# modbransv0_4_2.net
KiCad netlist of a schematic drawn in EAGLE
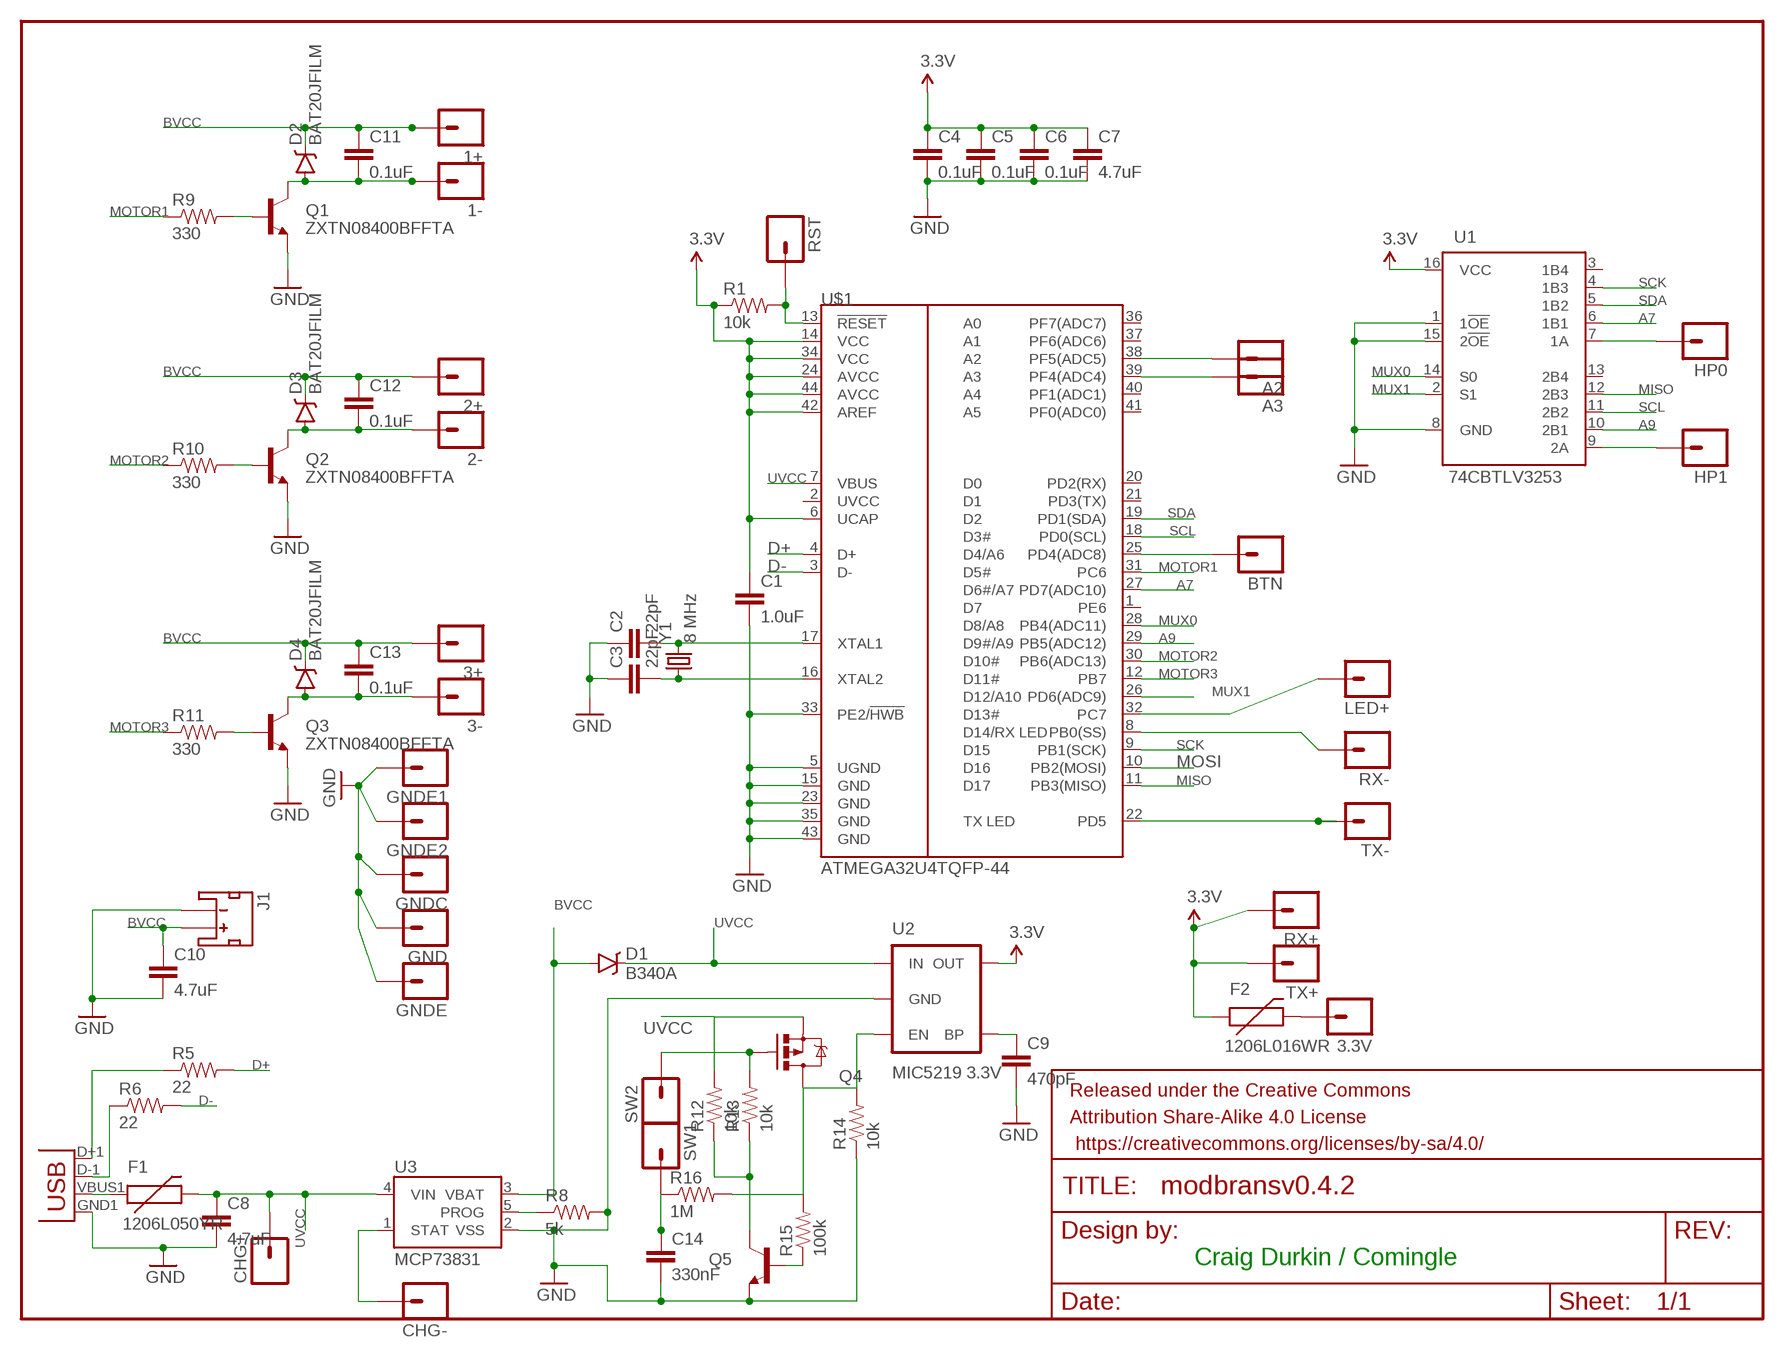
[diagram p0: schematic, sheet 1]

(export (version "E")
  (design (tool "Eeschema 10.0.6"))
  (components
    (comp (ref "1+")
      (value "M01PTH")
      (footprint "eagle-import:1X01")
      (libsource (lib "eagle-import") (part "M01PTH"))
    )
    (comp (ref "1-")
      (value "M01PTH")
      (footprint "eagle-import:1X01")
      (libsource (lib "eagle-import") (part "M01PTH"))
    )
    (comp (ref "2+")
      (value "M01PTH")
      (footprint "eagle-import:1X01")
      (libsource (lib "eagle-import") (part "M01PTH"))
    )
    (comp (ref "2-")
      (value "M01PTH")
      (footprint "eagle-import:1X01")
      (libsource (lib "eagle-import") (part "M01PTH"))
    )
    (comp (ref "3+")
      (value "M01PTH")
      (footprint "eagle-import:1X01")
      (libsource (lib "eagle-import") (part "M01PTH"))
    )
    (comp (ref "3-")
      (value "M01PTH")
      (footprint "eagle-import:1X01")
      (libsource (lib "eagle-import") (part "M01PTH"))
    )
    (comp (ref "3.3V")
      (value "M01PTH")
      (footprint "eagle-import:1X01")
      (libsource (lib "eagle-import") (part "M01PTH"))
    )
    (comp (ref "A2")
      (value "M01PTH")
      (footprint "eagle-import:1X01")
      (libsource (lib "eagle-import") (part "M01PTH"))
    )
    (comp (ref "A3")
      (value "M01PTH")
      (footprint "eagle-import:1X01")
      (libsource (lib "eagle-import") (part "M01PTH"))
    )
    (comp (ref "BTN")
      (value "M01PTH")
      (footprint "eagle-import:1X01")
      (libsource (lib "eagle-import") (part "M01PTH"))
    )
    (comp (ref "C1")
      (value "1.0uF")
      (footprint "eagle-import:0603-CAP")
      (libsource (lib "eagle-import") (part "CAP0603-CAP"))
    )
    (comp (ref "C2")
      (value "22pF")
      (footprint "eagle-import:0603-CAP")
      (libsource (lib "eagle-import") (part "CAP0603-CAP"))
    )
    (comp (ref "C3")
      (value "22pF")
      (footprint "eagle-import:0603-CAP")
      (libsource (lib "eagle-import") (part "CAP0603-CAP"))
    )
    (comp (ref "C4")
      (value "0.1uF")
      (footprint "eagle-import:0603-CAP")
      (libsource (lib "eagle-import") (part "SparkFun-Passives_CAP0603-CAP"))
    )
    (comp (ref "C5")
      (value "0.1uF")
      (footprint "eagle-import:0603-CAP")
      (libsource (lib "eagle-import") (part "SparkFun-Passives_CAP0603-CAP"))
    )
    (comp (ref "C6")
      (value "0.1uF")
      (footprint "eagle-import:0603-CAP")
      (libsource (lib "eagle-import") (part "SparkFun-Passives_CAP0603-CAP"))
    )
    (comp (ref "C7")
      (value "4.7uF")
      (footprint "eagle-import:0603-CAP")
      (libsource (lib "eagle-import") (part "SparkFun-Passives_CAP0603-CAP"))
    )
    (comp (ref "C8")
      (value "4.7uF")
      (footprint "eagle-import:1206")
      (libsource (lib "eagle-import") (part "SparkFun-Passives_CAP1206"))
    )
    (comp (ref "C9")
      (value "470pF")
      (footprint "eagle-import:0603-CAP")
      (libsource (lib "eagle-import") (part "CAP0603-CAP"))
    )
    (comp (ref "C10")
      (value "4.7uF")
      (footprint "eagle-import:1206")
      (libsource (lib "eagle-import") (part "SparkFun-Passives_CAP1206"))
    )
    (comp (ref "C11")
      (value "0.1uF")
      (footprint "eagle-import:0603-CAP")
      (libsource (lib "eagle-import") (part "CAP0603-CAP"))
    )
    (comp (ref "C12")
      (value "0.1uF")
      (footprint "eagle-import:0603-CAP")
      (libsource (lib "eagle-import") (part "CAP0603-CAP"))
    )
    (comp (ref "C13")
      (value "0.1uF")
      (footprint "eagle-import:0603-CAP")
      (libsource (lib "eagle-import") (part "CAP0603-CAP"))
    )
    (comp (ref "C14")
      (value "330nF")
      (footprint "eagle-import:0603-CAP")
      (libsource (lib "eagle-import") (part "CAP0603-CAP"))
    )
    (comp (ref "CHG+")
      (value "M01PTH")
      (footprint "eagle-import:1X01")
      (libsource (lib "eagle-import") (part "M01PTH"))
    )
    (comp (ref "CHG-")
      (value "M01PTH")
      (footprint "eagle-import:1X01")
      (libsource (lib "eagle-import") (part "M01PTH"))
    )
    (comp (ref "D1")
      (value "B340A")
      (footprint "eagle-import:SMA-DIODE")
      (libsource (lib "eagle-import") (part "DIODE-SCHOTTKY-B340A"))
    )
    (comp (ref "D2")
      (value "BAT20JFILM")
      (footprint "eagle-import:SOD-323")
      (libsource (lib "eagle-import") (part "BAT20JFILM"))
    )
    (comp (ref "D3")
      (value "BAT20JFILM")
      (footprint "eagle-import:SOD-323")
      (libsource (lib "eagle-import") (part "BAT20JFILM"))
    )
    (comp (ref "D4")
      (value "BAT20JFILM")
      (footprint "eagle-import:SOD-323")
      (libsource (lib "eagle-import") (part "BAT20JFILM"))
    )
    (comp (ref "F1")
      (value "1206L050YR")
      (footprint "eagle-import:PTC-1206")
      (libsource (lib "eagle-import") (part "PTCSMD"))
    )
    (comp (ref "F2")
      (value "1206L016WR")
      (footprint "eagle-import:PTC-1206")
      (libsource (lib "eagle-import") (part "PTCSMD"))
    )
    (comp (ref "FRAME1")
      (value "FRAME-LETTER")
      (footprint "eagle-import:CREATIVE_COMMONS")
      (libsource (lib "eagle-import") (part "FRAME-LETTER"))
    )
    (comp (ref "GND")
      (value "M01PTH")
      (footprint "eagle-import:1X01")
      (libsource (lib "eagle-import") (part "M01PTH"))
    )
    (comp (ref "GNDC")
      (value "M01PTH")
      (footprint "eagle-import:1X01")
      (libsource (lib "eagle-import") (part "M01PTH"))
    )
    (comp (ref "GNDE")
      (value "M01PTH")
      (footprint "eagle-import:1X01")
      (libsource (lib "eagle-import") (part "M01PTH"))
    )
    (comp (ref "GNDE1")
      (value "M01PTH")
      (footprint "eagle-import:1X01")
      (libsource (lib "eagle-import") (part "M01PTH"))
    )
    (comp (ref "GNDE2")
      (value "M01PTH")
      (footprint "eagle-import:1X01")
      (libsource (lib "eagle-import") (part "M01PTH"))
    )
    (comp (ref "HP0")
      (value "M01PTH")
      (footprint "eagle-import:1X01")
      (libsource (lib "eagle-import") (part "M01PTH"))
    )
    (comp (ref "HP1")
      (value "M01PTH")
      (footprint "eagle-import:1X01")
      (libsource (lib "eagle-import") (part "M01PTH"))
    )
    (comp (ref "J1")
      (value "JST_2MM_MALE")
      (footprint "eagle-import:JST-2-SMD")
      (libsource (lib "eagle-import") (part "JST_2MM_MALE"))
    )
    (comp (ref "JP4")
      (value "USB")
      (footprint "eagle-import:USB-B-MICRO-SMD_V03")
      (libsource (lib "eagle-import") (part "USB"))
    )
    (comp (ref "LED+")
      (value "M01PTH")
      (footprint "eagle-import:1X01")
      (libsource (lib "eagle-import") (part "M01PTH"))
    )
    (comp (ref "Q1")
      (value "ZXTN08400BFFTA")
      (footprint "eagle-import:SOT23-3")
      (libsource (lib "eagle-import") (part "TRANSISTOR_NPNSOT23-3"))
    )
    (comp (ref "Q2")
      (value "ZXTN08400BFFTA")
      (footprint "eagle-import:SOT23-3")
      (libsource (lib "eagle-import") (part "TRANSISTOR_NPNSOT23-3"))
    )
    (comp (ref "Q3")
      (value "ZXTN08400BFFTA")
      (footprint "eagle-import:SOT23-3")
      (libsource (lib "eagle-import") (part "TRANSISTOR_NPNSOT23-3"))
    )
    (comp (ref "Q4")
      (value "NTS2101PT1G")
      (footprint "eagle-import:SOT23-3")
      (libsource (lib "eagle-import") (part "MOSFET-PCHANNEL"))
    )
    (comp (ref "Q5")
      (value "MMBT2222A")
      (footprint "eagle-import:SOT23-3")
      (libsource (lib "eagle-import") (part "TRANSISTOR_NPNMMBT2222A"))
    )
    (comp (ref "R1")
      (value "10k")
      (footprint "eagle-import:0603-RES")
      (libsource (lib "eagle-import") (part "RESISTOR0603-RES"))
    )
    (comp (ref "R5")
      (value "22")
      (footprint "eagle-import:0603-RES")
      (libsource (lib "eagle-import") (part "RESISTOR0603-RES"))
    )
    (comp (ref "R6")
      (value "22")
      (footprint "eagle-import:0603-RES")
      (libsource (lib "eagle-import") (part "RESISTOR0603-RES"))
    )
    (comp (ref "R8")
      (value "5k")
      (footprint "eagle-import:0603-RES")
      (libsource (lib "eagle-import") (part "RESISTOR0603-RES"))
    )
    (comp (ref "R9")
      (value "330")
      (footprint "eagle-import:0603-RES")
      (libsource (lib "eagle-import") (part "RESISTOR0603-RES"))
    )
    (comp (ref "R10")
      (value "330")
      (footprint "eagle-import:0603-RES")
      (libsource (lib "eagle-import") (part "RESISTOR0603-RES"))
    )
    (comp (ref "R11")
      (value "330")
      (footprint "eagle-import:0603-RES")
      (libsource (lib "eagle-import") (part "RESISTOR0603-RES"))
    )
    (comp (ref "R12")
      (value "10k")
      (footprint "eagle-import:0603-RES")
      (libsource (lib "eagle-import") (part "RESISTOR0603-RES"))
    )
    (comp (ref "R13")
      (value "10k")
      (footprint "eagle-import:0603-RES")
      (libsource (lib "eagle-import") (part "RESISTOR0603-RES"))
    )
    (comp (ref "R14")
      (value "10k")
      (footprint "eagle-import:0603-RES")
      (libsource (lib "eagle-import") (part "RESISTOR0603-RES"))
    )
    (comp (ref "R15")
      (value "100k")
      (footprint "eagle-import:0603-RES")
      (libsource (lib "eagle-import") (part "RESISTOR0603-RES"))
    )
    (comp (ref "R16")
      (value "1M")
      (footprint "eagle-import:0603-RES")
      (libsource (lib "eagle-import") (part "RESISTOR0603-RES"))
    )
    (comp (ref "RST")
      (value "M01PTH")
      (footprint "eagle-import:1X01")
      (libsource (lib "eagle-import") (part "M01PTH"))
    )
    (comp (ref "RX+")
      (value "M01PTH")
      (footprint "eagle-import:1X01")
      (libsource (lib "eagle-import") (part "M01PTH"))
    )
    (comp (ref "RX-")
      (value "M01PTH")
      (footprint "eagle-import:1X01")
      (libsource (lib "eagle-import") (part "M01PTH"))
    )
    (comp (ref "SW1")
      (value "M01PTH")
      (footprint "eagle-import:1X01")
      (libsource (lib "eagle-import") (part "M01PTH"))
    )
    (comp (ref "SW2")
      (value "M01PTH")
      (footprint "eagle-import:1X01")
      (libsource (lib "eagle-import") (part "M01PTH"))
    )
    (comp (ref "TX+")
      (value "M01PTH")
      (footprint "eagle-import:1X01")
      (libsource (lib "eagle-import") (part "M01PTH"))
    )
    (comp (ref "TX-")
      (value "M01PTH")
      (footprint "eagle-import:1X01")
      (libsource (lib "eagle-import") (part "M01PTH"))
    )
    (comp (ref "U$1")
      (value "ATMEGA32U4TQFP-44")
      (footprint "eagle-import:TQFP44")
      (libsource (lib "eagle-import") (part "ATMEGA32U4TQFP-44"))
    )
    (comp (ref "U1")
      (value "74CBTLV3253")
      (footprint "eagle-import:SSOP16-PRACTICE")
      (libsource (lib "eagle-import") (part "74CBTLV3253"))
    )
    (comp (ref "U2")
      (value "MIC5219 3.3V")
      (footprint "eagle-import:SOT23-5")
      (libsource (lib "eagle-import") (part "V_REG_MIC52193.3V"))
    )
    (comp (ref "U3")
      (value "MCP73831")
      (footprint "eagle-import:SOT23-5")
      (libsource (lib "eagle-import") (part "MCP73831"))
    )
    (comp (ref "Y1")
      (value "8 MHz")
      (footprint "eagle-import:CRYSTAL-SMD-5X3")
      (libsource (lib "eagle-import") (part "CRYSTAL5X3"))
    )
  )
  (nets
    (net (code "1") (name "/A7") (class "Default")
      (node (ref "U$1") (pin "27") (pinfunction "PD7(ADC10)_27") (pintype "bidirectional"))
      (node (ref "U1") (pin "6") (pinfunction "1B1_6") (pintype "bidirectional"))
    )
    (net (code "2") (name "/A9") (class "Default")
      (node (ref "U$1") (pin "29") (pinfunction "PB5(ADC12)_29") (pintype "bidirectional"))
      (node (ref "U1") (pin "10") (pinfunction "2B1_10") (pintype "bidirectional"))
    )
    (net (code "3") (name "/BVCC") (class "Default")
      (node (ref "1+") (pin "1") (pinfunction "1_1") (pintype "passive"))
      (node (ref "2+") (pin "1") (pinfunction "1_1") (pintype "passive"))
      (node (ref "3+") (pin "1") (pinfunction "1_1") (pintype "passive"))
      (node (ref "C10") (pin "1") (pinfunction "1_1") (pintype "passive"))
      (node (ref "C11") (pin "1") (pinfunction "1_1") (pintype "passive"))
      (node (ref "C12") (pin "1") (pinfunction "1_1") (pintype "passive"))
      (node (ref "C13") (pin "1") (pinfunction "1_1") (pintype "passive"))
      (node (ref "D1") (pin "A") (pinfunction "A_A") (pintype "passive"))
      (node (ref "D2") (pin "C") (pinfunction "C_C") (pintype "passive"))
      (node (ref "D3") (pin "C") (pinfunction "C_C") (pintype "passive"))
      (node (ref "D4") (pin "C") (pinfunction "C_C") (pintype "passive"))
      (node (ref "J1") (pin "2") (pinfunction "+_2") (pintype "bidirectional"))
      (node (ref "U3") (pin "3") (pinfunction "VBAT_3") (pintype "power_in"))
    )
    (net (code "4") (name "/D+") (class "Default")
      (node (ref "R5") (pin "2") (pinfunction "2_2") (pintype "passive"))
      (node (ref "U$1") (pin "4") (pinfunction "D+_4") (pintype "bidirectional"))
    )
    (net (code "5") (name "/D-") (class "Default")
      (node (ref "R6") (pin "2") (pinfunction "2_2") (pintype "passive"))
      (node (ref "U$1") (pin "3") (pinfunction "D-_3") (pintype "bidirectional"))
    )
    (net (code "6") (name "/MISO") (class "Default")
      (node (ref "U$1") (pin "11") (pinfunction "PB3(MISO)_11") (pintype "bidirectional"))
      (node (ref "U1") (pin "12") (pinfunction "2B3_12") (pintype "bidirectional"))
    )
    (net (code "7") (name "/MOSI") (class "Default")
      (node (ref "U$1") (pin "10") (pinfunction "PB2(MOSI)_10") (pintype "bidirectional"))
    )
    (net (code "8") (name "/MOTOR1") (class "Default")
      (node (ref "R9") (pin "1") (pinfunction "1_1") (pintype "passive"))
      (node (ref "U$1") (pin "31") (pinfunction "PC6_31") (pintype "bidirectional"))
    )
    (net (code "9") (name "/MOTOR2") (class "Default")
      (node (ref "R10") (pin "1") (pinfunction "1_1") (pintype "passive"))
      (node (ref "U$1") (pin "30") (pinfunction "PB6(ADC13)_30") (pintype "bidirectional"))
    )
    (net (code "10") (name "/MOTOR3") (class "Default")
      (node (ref "R11") (pin "1") (pinfunction "1_1") (pintype "passive"))
      (node (ref "U$1") (pin "12") (pinfunction "PB7_12") (pintype "bidirectional"))
    )
    (net (code "11") (name "/MUX0") (class "Default")
      (node (ref "U$1") (pin "28") (pinfunction "PB4(ADC11)_28") (pintype "bidirectional"))
      (node (ref "U1") (pin "14") (pinfunction "S0_14") (pintype "bidirectional"))
    )
    (net (code "12") (name "/MUX1") (class "Default")
      (node (ref "U$1") (pin "26") (pinfunction "PD6(ADC9)_26") (pintype "bidirectional"))
      (node (ref "U1") (pin "2") (pinfunction "S1_2") (pintype "bidirectional"))
    )
    (net (code "13") (name "/SCK") (class "Default")
      (node (ref "U$1") (pin "9") (pinfunction "PB1(SCK)_9") (pintype "bidirectional"))
      (node (ref "U1") (pin "4") (pinfunction "1B3_4") (pintype "bidirectional"))
    )
    (net (code "14") (name "/SCL") (class "Default")
      (node (ref "U$1") (pin "18") (pinfunction "PD0(SCL)_18") (pintype "bidirectional"))
      (node (ref "U1") (pin "11") (pinfunction "2B2_11") (pintype "bidirectional"))
    )
    (net (code "15") (name "/SDA") (class "Default")
      (node (ref "U$1") (pin "19") (pinfunction "PD1(SDA)_19") (pintype "bidirectional"))
      (node (ref "U1") (pin "5") (pinfunction "1B2_5") (pintype "bidirectional"))
    )
    (net (code "16") (name "/UVCC") (class "Default")
      (node (ref "C8") (pin "1") (pinfunction "1_1") (pintype "passive"))
      (node (ref "CHG+") (pin "1") (pinfunction "1_1") (pintype "passive"))
      (node (ref "D1") (pin "C") (pinfunction "C_C") (pintype "passive"))
      (node (ref "F1") (pin "2") (pinfunction "2_2") (pintype "bidirectional"))
      (node (ref "Q4") (pin "2") (pinfunction "S_2") (pintype "passive"))
      (node (ref "R12") (pin "2") (pinfunction "2_2") (pintype "passive"))
      (node (ref "U$1") (pin "7") (pinfunction "VBUS_7") (pintype "bidirectional"))
      (node (ref "U2") (pin "1") (pinfunction "IN_1") (pintype "input"))
      (node (ref "U3") (pin "4") (pinfunction "VIN_4") (pintype "power_in"))
    )
    (net (code "17") (name "3.3V") (class "Default")
      (node (ref "C1") (pin "1") (pinfunction "1_1") (pintype "passive"))
      (node (ref "C4") (pin "1") (pinfunction "1_1") (pintype "passive"))
      (node (ref "C5") (pin "1") (pinfunction "1_1") (pintype "passive"))
      (node (ref "C6") (pin "1") (pinfunction "1_1") (pintype "passive"))
      (node (ref "C7") (pin "1") (pinfunction "1_1") (pintype "passive"))
      (node (ref "F2") (pin "1") (pinfunction "1_1") (pintype "bidirectional"))
      (node (ref "R1") (pin "1") (pinfunction "1_1") (pintype "passive"))
      (node (ref "RX+") (pin "1") (pinfunction "1_1") (pintype "passive"))
      (node (ref "TX+") (pin "1") (pinfunction "1_1") (pintype "passive"))
      (node (ref "U$1") (pin "14") (pinfunction "VCC_14") (pintype "bidirectional"))
      (node (ref "U$1") (pin "24") (pinfunction "AVCC_24") (pintype "bidirectional"))
      (node (ref "U$1") (pin "34") (pinfunction "VCC_34") (pintype "bidirectional"))
      (node (ref "U$1") (pin "42") (pinfunction "AREF_42") (pintype "bidirectional"))
      (node (ref "U$1") (pin "44") (pinfunction "AVCC_44") (pintype "bidirectional"))
      (node (ref "U$1") (pin "6") (pinfunction "UCAP_6") (pintype "bidirectional"))
      (node (ref "U1") (pin "16") (pinfunction "VCC_16") (pintype "power_in"))
      (node (ref "U2") (pin "5") (pinfunction "OUT_5") (pintype "passive"))
    )
    (net (code "18") (name "GND") (class "Default")
      (node (ref "C1") (pin "2") (pinfunction "2_2") (pintype "passive"))
      (node (ref "C10") (pin "2") (pinfunction "2_2") (pintype "passive"))
      (node (ref "C14") (pin "2") (pinfunction "2_2") (pintype "passive"))
      (node (ref "C2") (pin "1") (pinfunction "1_1") (pintype "passive"))
      (node (ref "C3") (pin "1") (pinfunction "1_1") (pintype "passive"))
      (node (ref "C4") (pin "2") (pinfunction "2_2") (pintype "passive"))
      (node (ref "C5") (pin "2") (pinfunction "2_2") (pintype "passive"))
      (node (ref "C6") (pin "2") (pinfunction "2_2") (pintype "passive"))
      (node (ref "C7") (pin "2") (pinfunction "2_2") (pintype "passive"))
      (node (ref "C8") (pin "2") (pinfunction "2_2") (pintype "passive"))
      (node (ref "C9") (pin "2") (pinfunction "2_2") (pintype "passive"))
      (node (ref "GND") (pin "1") (pinfunction "1_1") (pintype "passive"))
      (node (ref "GNDC") (pin "1") (pinfunction "1_1") (pintype "passive"))
      (node (ref "GNDE") (pin "1") (pinfunction "1_1") (pintype "passive"))
      (node (ref "GNDE1") (pin "1") (pinfunction "1_1") (pintype "passive"))
      (node (ref "GNDE2") (pin "1") (pinfunction "1_1") (pintype "passive"))
      (node (ref "J1") (pin "1") (pinfunction "-_1") (pintype "bidirectional"))
      (node (ref "JP4") (pin "GND1") (pinfunction "GND_GND1") (pintype "bidirectional"))
      (node (ref "Q1") (pin "2") (pinfunction "E_2") (pintype "passive"))
      (node (ref "Q2") (pin "2") (pinfunction "E_2") (pintype "passive"))
      (node (ref "Q3") (pin "2") (pinfunction "E_2") (pintype "passive"))
      (node (ref "Q5") (pin "2") (pinfunction "E_2") (pintype "passive"))
      (node (ref "R14") (pin "1") (pinfunction "1_1") (pintype "passive"))
      (node (ref "R8") (pin "2") (pinfunction "2_2") (pintype "passive"))
      (node (ref "U$1") (pin "15") (pinfunction "GND_15") (pintype "bidirectional"))
      (node (ref "U$1") (pin "23") (pinfunction "GND_23") (pintype "bidirectional"))
      (node (ref "U$1") (pin "33") (pinfunction "PE2/~{HWB}_33") (pintype "bidirectional"))
      (node (ref "U$1") (pin "35") (pinfunction "GND_35") (pintype "bidirectional"))
      (node (ref "U$1") (pin "43") (pinfunction "GND_43") (pintype "bidirectional"))
      (node (ref "U$1") (pin "5") (pinfunction "UGND_5") (pintype "bidirectional"))
      (node (ref "U1") (pin "1") (pinfunction "1~{OE}_1") (pintype "input"))
      (node (ref "U1") (pin "15") (pinfunction "2~{OE}_15") (pintype "input"))
      (node (ref "U1") (pin "8") (pinfunction "GND_8") (pintype "power_in"))
      (node (ref "U2") (pin "2") (pinfunction "GND_2") (pintype "input"))
      (node (ref "U3") (pin "2") (pinfunction "VSS_2") (pintype "power_in"))
    )
    (net (code "19") (name "Net-(3.3V-Pad1)") (class "Default")
      (node (ref "3.3V") (pin "1") (pinfunction "1_1") (pintype "passive"))
      (node (ref "F2") (pin "2") (pinfunction "2_2") (pintype "bidirectional"))
    )
    (net (code "20") (name "Net-(C14-Pad1)") (class "Default")
      (node (ref "C14") (pin "1") (pinfunction "1_1") (pintype "passive"))
      (node (ref "R16") (pin "1") (pinfunction "1_1") (pintype "passive"))
      (node (ref "SW1") (pin "1") (pinfunction "1_1") (pintype "passive"))
    )
    (net (code "21") (name "Net-(JP4-D+)") (class "Default")
      (node (ref "JP4") (pin "D+1") (pinfunction "D+_D+1") (pintype "bidirectional"))
      (node (ref "R5") (pin "1") (pinfunction "1_1") (pintype "passive"))
    )
    (net (code "22") (name "Net-(JP4-D-)") (class "Default")
      (node (ref "JP4") (pin "D-1") (pinfunction "D-_D-1") (pintype "bidirectional"))
      (node (ref "R6") (pin "1") (pinfunction "1_1") (pintype "passive"))
    )
    (net (code "23") (name "Net-(JP4-VBUS)") (class "Default")
      (node (ref "F1") (pin "1") (pinfunction "1_1") (pintype "bidirectional"))
      (node (ref "JP4") (pin "VBUS1") (pinfunction "VBUS_VBUS1") (pintype "bidirectional"))
    )
    (net (code "24") (name "Net-(Q1-B)") (class "Default")
      (node (ref "Q1") (pin "1") (pinfunction "B_1") (pintype "passive"))
      (node (ref "R9") (pin "2") (pinfunction "2_2") (pintype "passive"))
    )
    (net (code "25") (name "Net-(Q1-C)") (class "Default")
      (node (ref "1-") (pin "1") (pinfunction "1_1") (pintype "passive"))
      (node (ref "C11") (pin "2") (pinfunction "2_2") (pintype "passive"))
      (node (ref "D2") (pin "A") (pinfunction "A_A") (pintype "passive"))
      (node (ref "Q1") (pin "3") (pinfunction "C_3") (pintype "passive"))
    )
    (net (code "26") (name "Net-(Q2-B)") (class "Default")
      (node (ref "Q2") (pin "1") (pinfunction "B_1") (pintype "passive"))
      (node (ref "R10") (pin "2") (pinfunction "2_2") (pintype "passive"))
    )
    (net (code "27") (name "Net-(Q2-C)") (class "Default")
      (node (ref "2-") (pin "1") (pinfunction "1_1") (pintype "passive"))
      (node (ref "C12") (pin "2") (pinfunction "2_2") (pintype "passive"))
      (node (ref "D3") (pin "A") (pinfunction "A_A") (pintype "passive"))
      (node (ref "Q2") (pin "3") (pinfunction "C_3") (pintype "passive"))
    )
    (net (code "28") (name "Net-(Q3-B)") (class "Default")
      (node (ref "Q3") (pin "1") (pinfunction "B_1") (pintype "passive"))
      (node (ref "R11") (pin "2") (pinfunction "2_2") (pintype "passive"))
    )
    (net (code "29") (name "Net-(Q3-C)") (class "Default")
      (node (ref "3-") (pin "1") (pinfunction "1_1") (pintype "passive"))
      (node (ref "C13") (pin "2") (pinfunction "2_2") (pintype "passive"))
      (node (ref "D4") (pin "A") (pinfunction "A_A") (pintype "passive"))
      (node (ref "Q3") (pin "3") (pinfunction "C_3") (pintype "passive"))
    )
    (net (code "30") (name "Net-(Q4-D)") (class "Default")
      (node (ref "Q4") (pin "3") (pinfunction "D_3") (pintype "passive"))
      (node (ref "R14") (pin "2") (pinfunction "2_2") (pintype "passive"))
      (node (ref "R15") (pin "2") (pinfunction "2_2") (pintype "passive"))
      (node (ref "R16") (pin "2") (pinfunction "2_2") (pintype "passive"))
      (node (ref "U2") (pin "3") (pinfunction "EN_3") (pintype "input"))
    )
    (net (code "31") (name "Net-(Q4-G)") (class "Default")
      (node (ref "Q4") (pin "1") (pinfunction "G_1") (pintype "passive"))
      (node (ref "R13") (pin "2") (pinfunction "2_2") (pintype "passive"))
      (node (ref "SW2") (pin "1") (pinfunction "1_1") (pintype "passive"))
    )
    (net (code "32") (name "Net-(Q5-B)") (class "Default")
      (node (ref "Q5") (pin "1") (pinfunction "B_1") (pintype "passive"))
      (node (ref "R15") (pin "1") (pinfunction "1_1") (pintype "passive"))
    )
    (net (code "33") (name "Net-(Q5-C)") (class "Default")
      (node (ref "Q5") (pin "3") (pinfunction "C_3") (pintype "passive"))
      (node (ref "R12") (pin "1") (pinfunction "1_1") (pintype "passive"))
      (node (ref "R13") (pin "1") (pinfunction "1_1") (pintype "passive"))
    )
    (net (code "34") (name "Net-(U$1-PB0(SS))") (class "Default")
      (node (ref "RX-") (pin "1") (pinfunction "1_1") (pintype "passive"))
      (node (ref "U$1") (pin "8") (pinfunction "PB0(SS)_8") (pintype "bidirectional"))
    )
    (net (code "35") (name "Net-(U$1-PC7)") (class "Default")
      (node (ref "LED+") (pin "1") (pinfunction "1_1") (pintype "passive"))
      (node (ref "U$1") (pin "32") (pinfunction "PC7_32") (pintype "bidirectional"))
    )
    (net (code "36") (name "Net-(U$1-PD4(ADC8))") (class "Default")
      (node (ref "BTN") (pin "1") (pinfunction "1_1") (pintype "passive"))
      (node (ref "U$1") (pin "25") (pinfunction "PD4(ADC8)_25") (pintype "bidirectional"))
    )
    (net (code "37") (name "Net-(U$1-PD5)") (class "Default")
      (node (ref "TX-") (pin "1") (pinfunction "1_1") (pintype "passive"))
      (node (ref "U$1") (pin "22") (pinfunction "PD5_22") (pintype "bidirectional"))
    )
    (net (code "38") (name "Net-(U$1-PF4(ADC4))") (class "Default")
      (node (ref "A3") (pin "1") (pinfunction "1_1") (pintype "passive"))
      (node (ref "U$1") (pin "39") (pinfunction "PF4(ADC4)_39") (pintype "bidirectional"))
    )
    (net (code "39") (name "Net-(U$1-PF5(ADC5))") (class "Default")
      (node (ref "A2") (pin "1") (pinfunction "1_1") (pintype "passive"))
      (node (ref "U$1") (pin "38") (pinfunction "PF5(ADC5)_38") (pintype "bidirectional"))
    )
    (net (code "40") (name "Net-(U$1-XTAL1)") (class "Default")
      (node (ref "C2") (pin "2") (pinfunction "2_2") (pintype "passive"))
      (node (ref "U$1") (pin "17") (pinfunction "XTAL1_17") (pintype "bidirectional"))
      (node (ref "Y1") (pin "3") (pinfunction "2_3") (pintype "passive"))
    )
    (net (code "41") (name "Net-(U$1-XTAL2)") (class "Default")
      (node (ref "C3") (pin "2") (pinfunction "2_2") (pintype "passive"))
      (node (ref "U$1") (pin "16") (pinfunction "XTAL2_16") (pintype "bidirectional"))
      (node (ref "Y1") (pin "1") (pinfunction "1_1") (pintype "passive"))
    )
    (net (code "42") (name "Net-(U$1-~{RESET})") (class "Default")
      (node (ref "R1") (pin "2") (pinfunction "2_2") (pintype "passive"))
      (node (ref "RST") (pin "1") (pinfunction "1_1") (pintype "passive"))
      (node (ref "U$1") (pin "13") (pinfunction "~{RESET}_13") (pintype "bidirectional"))
    )
    (net (code "43") (name "Net-(U1-1A)") (class "Default")
      (node (ref "HP0") (pin "1") (pinfunction "1_1") (pintype "passive"))
      (node (ref "U1") (pin "7") (pinfunction "1A_7") (pintype "bidirectional"))
    )
    (net (code "44") (name "Net-(U1-2A)") (class "Default")
      (node (ref "HP1") (pin "1") (pinfunction "1_1") (pintype "passive"))
      (node (ref "U1") (pin "9") (pinfunction "2A_9") (pintype "bidirectional"))
    )
    (net (code "45") (name "Net-(U2-BP)") (class "Default")
      (node (ref "C9") (pin "1") (pinfunction "1_1") (pintype "passive"))
      (node (ref "U2") (pin "4") (pinfunction "BP_4") (pintype "input"))
    )
    (net (code "46") (name "Net-(U3-PROG)") (class "Default")
      (node (ref "R8") (pin "1") (pinfunction "1_1") (pintype "passive"))
      (node (ref "U3") (pin "5") (pinfunction "PROG_5") (pintype "bidirectional"))
    )
    (net (code "47") (name "Net-(U3-STAT)") (class "Default")
      (node (ref "CHG-") (pin "1") (pinfunction "1_1") (pintype "passive"))
      (node (ref "U3") (pin "1") (pinfunction "STAT_1") (pintype "output"))
    )
    (net (code "48") (name "unconnected-(J1-PAD1-PadNC1)") (class "Default")
      (node (ref "J1") (pin "NC1") (pinfunction "PAD1_NC1") (pintype "bidirectional"))
    )
    (net (code "49") (name "unconnected-(J1-PAD2-PadNC2)") (class "Default")
      (node (ref "J1") (pin "NC2") (pinfunction "PAD2_NC2") (pintype "bidirectional"))
    )
    (net (code "50") (name "unconnected-(U$1-PD2(RX)-Pad20)") (class "Default")
      (node (ref "U$1") (pin "20") (pinfunction "PD2(RX)_20") (pintype "bidirectional"))
    )
    (net (code "51") (name "unconnected-(U$1-PD3(TX)-Pad21)") (class "Default")
      (node (ref "U$1") (pin "21") (pinfunction "PD3(TX)_21") (pintype "bidirectional"))
    )
    (net (code "52") (name "unconnected-(U$1-PE6-Pad1)") (class "Default")
      (node (ref "U$1") (pin "1") (pinfunction "PE6_1") (pintype "bidirectional"))
    )
    (net (code "53") (name "unconnected-(U$1-PF0(ADC0)-Pad41)") (class "Default")
      (node (ref "U$1") (pin "41") (pinfunction "PF0(ADC0)_41") (pintype "bidirectional"))
    )
    (net (code "54") (name "unconnected-(U$1-PF1(ADC1)-Pad40)") (class "Default")
      (node (ref "U$1") (pin "40") (pinfunction "PF1(ADC1)_40") (pintype "bidirectional"))
    )
    (net (code "55") (name "unconnected-(U$1-PF6(ADC6)-Pad37)") (class "Default")
      (node (ref "U$1") (pin "37") (pinfunction "PF6(ADC6)_37") (pintype "bidirectional"))
    )
    (net (code "56") (name "unconnected-(U$1-PF7(ADC7)-Pad36)") (class "Default")
      (node (ref "U$1") (pin "36") (pinfunction "PF7(ADC7)_36") (pintype "bidirectional"))
    )
    (net (code "57") (name "unconnected-(U$1-UVCC-Pad2)") (class "Default")
      (node (ref "U$1") (pin "2") (pinfunction "UVCC_2") (pintype "bidirectional"))
    )
    (net (code "58") (name "unconnected-(U1-1B4-Pad3)") (class "Default")
      (node (ref "U1") (pin "3") (pinfunction "1B4_3") (pintype "bidirectional"))
    )
    (net (code "59") (name "unconnected-(U1-2B4-Pad13)") (class "Default")
      (node (ref "U1") (pin "13") (pinfunction "2B4_13") (pintype "bidirectional"))
    )
  )
)
